# LaserZ-V2.net
KiCad netlist of a schematic drawn in EAGLE
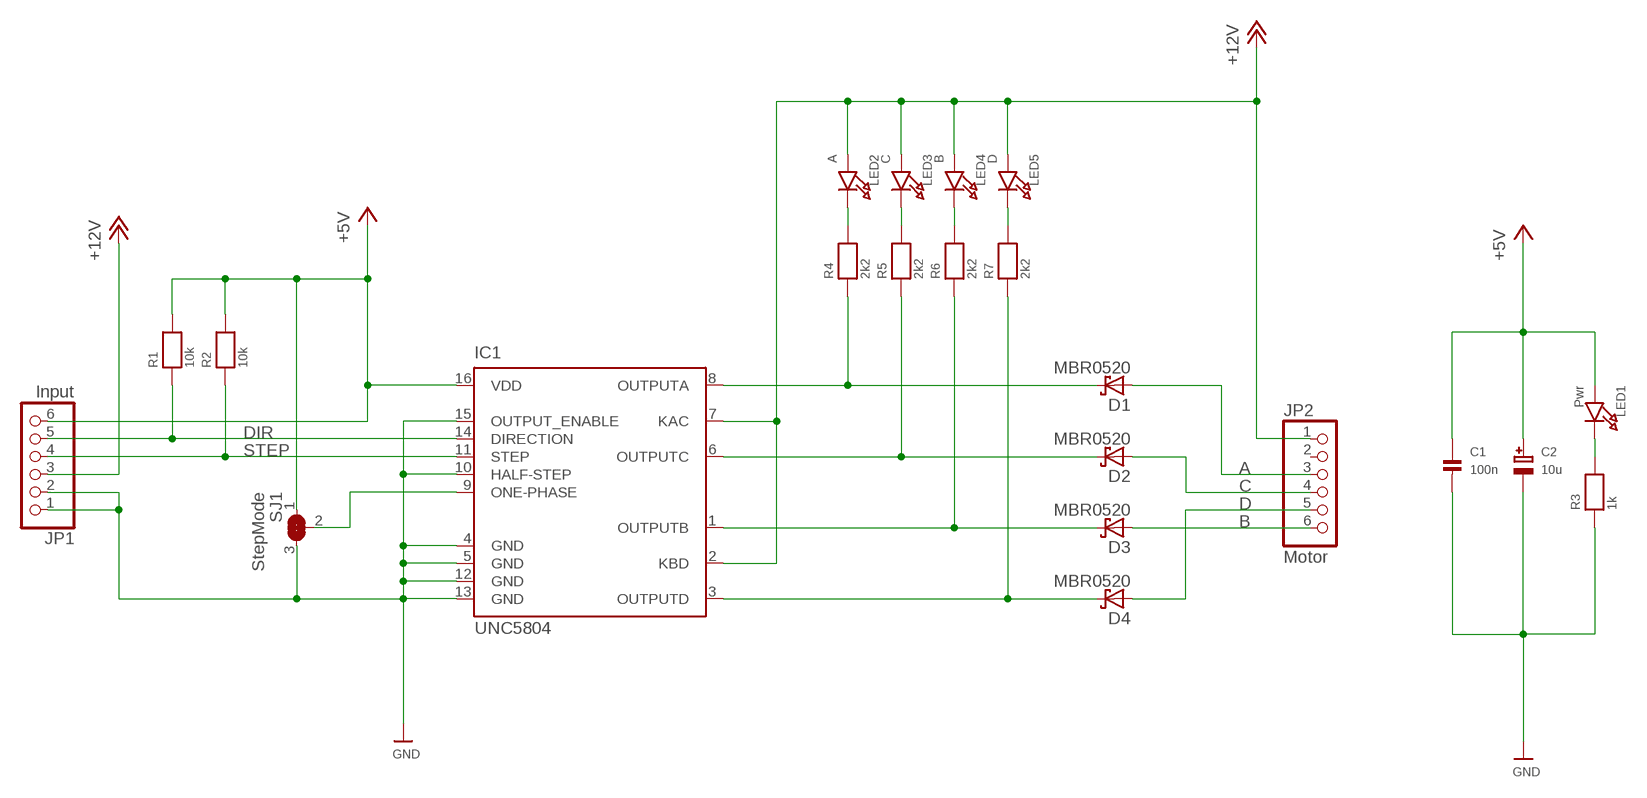
[diagram p0: schematic, sheet 1]

(export (version "E")
  (design (tool "Eeschema 10.0.6"))
  (components
    (comp (ref "C1")
      (value "100n")
      (footprint "eagle-import:0805")
      (libsource (lib "eagle-import") (part "CAP_CERAMIC0805"))
    )
    (comp (ref "C2")
      (value "10u")
      (footprint "eagle-import:EIA3216-18_A-W")
      (libsource (lib "eagle-import") (part "CAP_TANTALUMA/3216_WAVE"))
    )
    (comp (ref "D1")
      (value "MBR0520")
      (footprint "eagle-import:SOD123")
      (libsource (lib "eagle-import") (part "MBR0520"))
    )
    (comp (ref "D2")
      (value "MBR0520")
      (footprint "eagle-import:SOD123")
      (libsource (lib "eagle-import") (part "MBR0520"))
    )
    (comp (ref "D3")
      (value "MBR0520")
      (footprint "eagle-import:SOD123")
      (libsource (lib "eagle-import") (part "MBR0520"))
    )
    (comp (ref "D4")
      (value "MBR0520")
      (footprint "eagle-import:SOD123")
      (libsource (lib "eagle-import") (part "MBR0520"))
    )
    (comp (ref "IC1")
      (value "UNC5804")
      (footprint "eagle-import:SO-16DW")
      (libsource (lib "eagle-import") (part "UNC5804LB"))
    )
    (comp (ref "JP1")
      (value "Input")
      (footprint "eagle-import:1X06")
      (libsource (lib "eagle-import") (part "PINHD-1X6"))
    )
    (comp (ref "JP2")
      (value "Motor")
      (footprint "eagle-import:1X06")
      (libsource (lib "eagle-import") (part "PINHD-1X6"))
    )
    (comp (ref "LED1")
      (value "Pwr")
      (footprint "eagle-import:CHIPLED_0805")
      (libsource (lib "eagle-import") (part "LED0805"))
    )
    (comp (ref "LED2")
      (value "A")
      (footprint "eagle-import:CHIPLED_0805")
      (libsource (lib "eagle-import") (part "LED0805"))
    )
    (comp (ref "LED3")
      (value "C")
      (footprint "eagle-import:CHIPLED_0805")
      (libsource (lib "eagle-import") (part "LED0805"))
    )
    (comp (ref "LED4")
      (value "B")
      (footprint "eagle-import:CHIPLED_0805")
      (libsource (lib "eagle-import") (part "LED0805"))
    )
    (comp (ref "LED5")
      (value "D")
      (footprint "eagle-import:CHIPLED_0805")
      (libsource (lib "eagle-import") (part "LED0805"))
    )
    (comp (ref "R1")
      (value "10k")
      (footprint "eagle-import:0805")
      (libsource (lib "eagle-import") (part "RESISTOR0805"))
    )
    (comp (ref "R2")
      (value "10k")
      (footprint "eagle-import:0805")
      (libsource (lib "eagle-import") (part "RESISTOR0805"))
    )
    (comp (ref "R3")
      (value "1k")
      (footprint "eagle-import:0805")
      (libsource (lib "eagle-import") (part "RESISTOR0805"))
    )
    (comp (ref "R4")
      (value "2k2")
      (footprint "eagle-import:0805")
      (libsource (lib "eagle-import") (part "RESISTOR0805"))
    )
    (comp (ref "R5")
      (value "2k2")
      (footprint "eagle-import:0805")
      (libsource (lib "eagle-import") (part "RESISTOR0805"))
    )
    (comp (ref "R6")
      (value "2k2")
      (footprint "eagle-import:0805")
      (libsource (lib "eagle-import") (part "RESISTOR0805"))
    )
    (comp (ref "R7")
      (value "2k2")
      (footprint "eagle-import:0805")
      (libsource (lib "eagle-import") (part "RESISTOR0805"))
    )
    (comp (ref "SJ1")
      (value "StepMode")
      (footprint "eagle-import:SOLDERJUMPER_2WAY_OPEN_NOPASTE")
      (libsource (lib "eagle-import") (part "SOLDERJUMPER_2WAY"))
    )
  )
  (nets
    (net (code "1") (name "+5V") (class "Default")
      (node (ref "C1") (pin "1") (pinfunction "P$1_1") (pintype "passive"))
      (node (ref "C2") (pin "+") (pinfunction "+_+") (pintype "passive"))
      (node (ref "IC1") (pin "16") (pinfunction "VDD_16") (pintype "power_in"))
      (node (ref "JP1") (pin "6") (pinfunction "6_6") (pintype "passive"))
      (node (ref "LED1") (pin "A") (pinfunction "A_A") (pintype "passive"))
      (node (ref "R1") (pin "2") (pinfunction "2_2") (pintype "passive"))
      (node (ref "R2") (pin "2") (pinfunction "2_2") (pintype "passive"))
      (node (ref "SJ1") (pin "1") (pinfunction "1_1") (pintype "passive"))
    )
    (net (code "2") (name "+12V") (class "Default")
      (node (ref "IC1") (pin "2") (pinfunction "KBD_2") (pintype "passive"))
      (node (ref "IC1") (pin "7") (pinfunction "KAC_7") (pintype "passive"))
      (node (ref "JP1") (pin "3") (pinfunction "3_3") (pintype "passive"))
      (node (ref "JP2") (pin "1") (pinfunction "1_1") (pintype "passive"))
      (node (ref "LED2") (pin "A") (pinfunction "A_A") (pintype "passive"))
      (node (ref "LED3") (pin "A") (pinfunction "A_A") (pintype "passive"))
      (node (ref "LED4") (pin "A") (pinfunction "A_A") (pintype "passive"))
      (node (ref "LED5") (pin "A") (pinfunction "A_A") (pintype "passive"))
    )
    (net (code "3") (name "/A") (class "Default")
      (node (ref "D1") (pin "A") (pinfunction "A_A") (pintype "passive"))
      (node (ref "JP2") (pin "3") (pinfunction "3_3") (pintype "passive"))
    )
    (net (code "4") (name "/B") (class "Default")
      (node (ref "D3") (pin "A") (pinfunction "A_A") (pintype "passive"))
      (node (ref "JP2") (pin "6") (pinfunction "6_6") (pintype "passive"))
    )
    (net (code "5") (name "/C") (class "Default")
      (node (ref "D2") (pin "A") (pinfunction "A_A") (pintype "passive"))
      (node (ref "JP2") (pin "4") (pinfunction "4_4") (pintype "passive"))
    )
    (net (code "6") (name "/D") (class "Default")
      (node (ref "D4") (pin "A") (pinfunction "A_A") (pintype "passive"))
      (node (ref "JP2") (pin "5") (pinfunction "5_5") (pintype "passive"))
    )
    (net (code "7") (name "/DIR") (class "Default")
      (node (ref "IC1") (pin "14") (pinfunction "DIRECTION_14") (pintype "input"))
      (node (ref "JP1") (pin "5") (pinfunction "5_5") (pintype "passive"))
      (node (ref "R1") (pin "1") (pinfunction "1_1") (pintype "passive"))
    )
    (net (code "8") (name "/STEP") (class "Default")
      (node (ref "IC1") (pin "11") (pinfunction "STEP_11") (pintype "input"))
      (node (ref "JP1") (pin "4") (pinfunction "4_4") (pintype "passive"))
      (node (ref "R2") (pin "1") (pinfunction "1_1") (pintype "passive"))
    )
    (net (code "9") (name "GND") (class "Default")
      (node (ref "C1") (pin "2") (pinfunction "P$2_2") (pintype "passive"))
      (node (ref "C2") (pin "-") (pinfunction "-_-") (pintype "passive"))
      (node (ref "IC1") (pin "10") (pinfunction "HALF-STEP_10") (pintype "input"))
      (node (ref "IC1") (pin "12") (pinfunction "GND_12") (pintype "power_in"))
      (node (ref "IC1") (pin "13") (pinfunction "GND_13") (pintype "power_in"))
      (node (ref "IC1") (pin "15") (pinfunction "OUTPUT_ENABLE_15") (pintype "input"))
      (node (ref "IC1") (pin "4") (pinfunction "GND_4") (pintype "power_in"))
      (node (ref "IC1") (pin "5") (pinfunction "GND_5") (pintype "power_in"))
      (node (ref "JP1") (pin "1") (pinfunction "1_1") (pintype "passive"))
      (node (ref "JP1") (pin "2") (pinfunction "2_2") (pintype "passive"))
      (node (ref "R3") (pin "1") (pinfunction "1_1") (pintype "passive"))
      (node (ref "SJ1") (pin "3") (pinfunction "3_3") (pintype "passive"))
    )
    (net (code "10") (name "Net-(IC1-ONE-PHASE)") (class "Default")
      (node (ref "IC1") (pin "9") (pinfunction "ONE-PHASE_9") (pintype "input"))
      (node (ref "SJ1") (pin "2") (pinfunction "2_2") (pintype "passive"))
    )
    (net (code "11") (name "Net-(IC1-OUTPUTA)") (class "Default")
      (node (ref "D1") (pin "C") (pinfunction "C_C") (pintype "passive"))
      (node (ref "IC1") (pin "8") (pinfunction "OUTPUTA_8") (pintype "output"))
      (node (ref "R4") (pin "1") (pinfunction "1_1") (pintype "passive"))
    )
    (net (code "12") (name "Net-(IC1-OUTPUTB)") (class "Default")
      (node (ref "D3") (pin "C") (pinfunction "C_C") (pintype "passive"))
      (node (ref "IC1") (pin "1") (pinfunction "OUTPUTB_1") (pintype "output"))
      (node (ref "R6") (pin "1") (pinfunction "1_1") (pintype "passive"))
    )
    (net (code "13") (name "Net-(IC1-OUTPUTC)") (class "Default")
      (node (ref "D2") (pin "C") (pinfunction "C_C") (pintype "passive"))
      (node (ref "IC1") (pin "6") (pinfunction "OUTPUTC_6") (pintype "output"))
      (node (ref "R5") (pin "1") (pinfunction "1_1") (pintype "passive"))
    )
    (net (code "14") (name "Net-(IC1-OUTPUTD)") (class "Default")
      (node (ref "D4") (pin "C") (pinfunction "C_C") (pintype "passive"))
      (node (ref "IC1") (pin "3") (pinfunction "OUTPUTD_3") (pintype "output"))
      (node (ref "R7") (pin "1") (pinfunction "1_1") (pintype "passive"))
    )
    (net (code "15") (name "Net-(LED1-PadC)") (class "Default")
      (node (ref "LED1") (pin "C") (pinfunction "C_C") (pintype "passive"))
      (node (ref "R3") (pin "2") (pinfunction "2_2") (pintype "passive"))
    )
    (net (code "16") (name "Net-(LED2-PadC)") (class "Default")
      (node (ref "LED2") (pin "C") (pinfunction "C_C") (pintype "passive"))
      (node (ref "R4") (pin "2") (pinfunction "2_2") (pintype "passive"))
    )
    (net (code "17") (name "Net-(LED3-PadC)") (class "Default")
      (node (ref "LED3") (pin "C") (pinfunction "C_C") (pintype "passive"))
      (node (ref "R5") (pin "2") (pinfunction "2_2") (pintype "passive"))
    )
    (net (code "18") (name "Net-(LED4-PadC)") (class "Default")
      (node (ref "LED4") (pin "C") (pinfunction "C_C") (pintype "passive"))
      (node (ref "R6") (pin "2") (pinfunction "2_2") (pintype "passive"))
    )
    (net (code "19") (name "Net-(LED5-PadC)") (class "Default")
      (node (ref "LED5") (pin "C") (pinfunction "C_C") (pintype "passive"))
      (node (ref "R7") (pin "2") (pinfunction "2_2") (pintype "passive"))
    )
    (net (code "20") (name "unconnected-(JP2-Pad2)") (class "Default")
      (node (ref "JP2") (pin "2") (pinfunction "2_2") (pintype "passive"))
    )
  )
)
